# Boost_Converter.net
KiCad netlist of a schematic drawn in Altium Designer
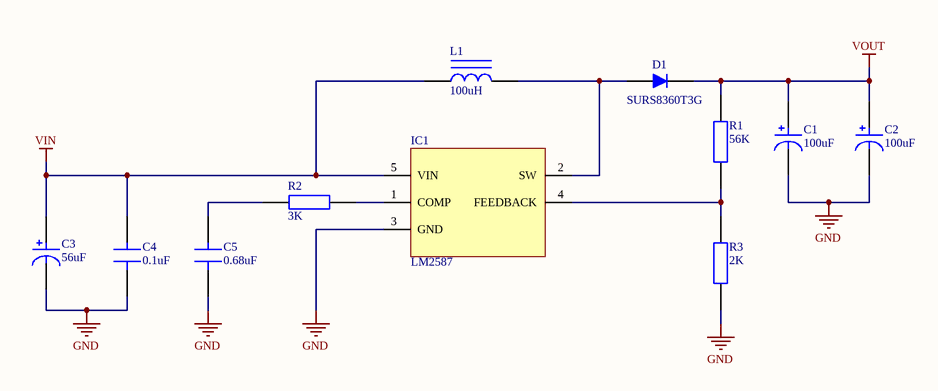
[diagram p0: Boost Converter.SchDoc]

(export (version "E")
  (design (tool "Eeschema 10.0.6"))
  (components
    (comp (ref "C1")
      (value "100uF")
      (footprint "EEE-FK1H101P")
      (libsource (lib "Boost Converter") (part "100uF"))
    )
    (comp (ref "C2")
      (value "100uF")
      (footprint "EEE-FK1H101P")
      (libsource (lib "Boost Converter") (part "100uF"))
    )
    (comp (ref "C3")
      (value "56uF")
      (footprint "UWD1V560MCL1GS")
      (libsource (lib "Boost Converter") (part "56uF"))
    )
    (comp (ref "C4")
      (value "0.1uF")
      (footprint "CAP-0805")
      (libsource (lib "Boost Converter") (part "0.1uF"))
    )
    (comp (ref "C5")
      (value "0.68uF")
      (footprint "CAP-0805")
      (libsource (lib "Boost Converter") (part "0.68uF"))
    )
    (comp (ref "D1")
      (value "SURS8360T3G")
      (footprint "SURS8360")
      (libsource (lib "Boost Converter") (part "SURS8360T3G"))
    )
    (comp (ref "IC1")
      (value "LM2587")
      (footprint "D2PAK")
      (libsource (lib "Boost Converter") (part "LM2587"))
    )
    (comp (ref "L1") (value "100uH") (footprint "7447070") (libsource (lib "Boost Converter") (part "100uH")))
    (comp (ref "R1") (value "56K") (footprint "RES-0805") (libsource (lib "Boost Converter") (part "56K")))
    (comp (ref "R2") (value "3K") (footprint "RES-0805") (libsource (lib "Boost Converter") (part "3K")))
    (comp (ref "R3") (value "2K") (footprint "RES-0805") (libsource (lib "Boost Converter") (part "2K")))
  )
  (nets
    (net (code "1") (name "GND") (class "Default")
      (node (ref "C1") (pin "2") (pinfunction "2_2") (pintype "passive"))
      (node (ref "C2") (pin "2") (pinfunction "2_2") (pintype "passive"))
      (node (ref "C3") (pin "2") (pinfunction "2_2") (pintype "passive"))
      (node (ref "C4") (pin "1") (pinfunction "1_1") (pintype "passive"))
      (node (ref "C5") (pin "1") (pinfunction "1_1") (pintype "passive"))
      (node (ref "IC1") (pin "3") (pinfunction "GND_3") (pintype "passive"))
      (node (ref "R3") (pin "1") (pinfunction "1_1") (pintype "passive"))
    )
    (net (code "2") (name "Net-(C5-Pad2)") (class "Default")
      (node (ref "C5") (pin "2") (pinfunction "2_2") (pintype "passive"))
      (node (ref "R2") (pin "1") (pinfunction "1_1") (pintype "passive"))
    )
    (net (code "3") (name "Net-(IC1-COMP)") (class "Default")
      (node (ref "IC1") (pin "1") (pinfunction "COMP_1") (pintype "passive"))
      (node (ref "R2") (pin "2") (pinfunction "2_2") (pintype "passive"))
    )
    (net (code "4") (name "Net-(IC1-FEEDBACK)") (class "Default")
      (node (ref "IC1") (pin "4") (pinfunction "FEEDBACK_4") (pintype "passive"))
      (node (ref "R1") (pin "1") (pinfunction "1_1") (pintype "passive"))
      (node (ref "R3") (pin "2") (pinfunction "2_2") (pintype "passive"))
    )
    (net (code "5") (name "Net-(IC1-SW)") (class "Default")
      (node (ref "D1") (pin "1") (pinfunction "1_1") (pintype "passive"))
      (node (ref "IC1") (pin "2") (pinfunction "SW_2") (pintype "passive"))
      (node (ref "L1") (pin "2") (pinfunction "2_2") (pintype "passive"))
    )
    (net (code "6") (name "VIN") (class "Default")
      (node (ref "C3") (pin "1") (pinfunction "1_1") (pintype "passive"))
      (node (ref "C4") (pin "2") (pinfunction "2_2") (pintype "passive"))
      (node (ref "IC1") (pin "5") (pinfunction "VIN_5") (pintype "passive"))
      (node (ref "L1") (pin "1") (pinfunction "1_1") (pintype "passive"))
    )
    (net (code "7") (name "VOUT") (class "Default")
      (node (ref "C1") (pin "1") (pinfunction "1_1") (pintype "passive"))
      (node (ref "C2") (pin "1") (pinfunction "1_1") (pintype "passive"))
      (node (ref "D1") (pin "2") (pinfunction "2_2") (pintype "passive"))
      (node (ref "R1") (pin "2") (pinfunction "2_2") (pintype "passive"))
    )
  )
)
